# simplePDschematicsv1_AZ_SMD.net
KiCad netlist of a schematic drawn in EAGLE
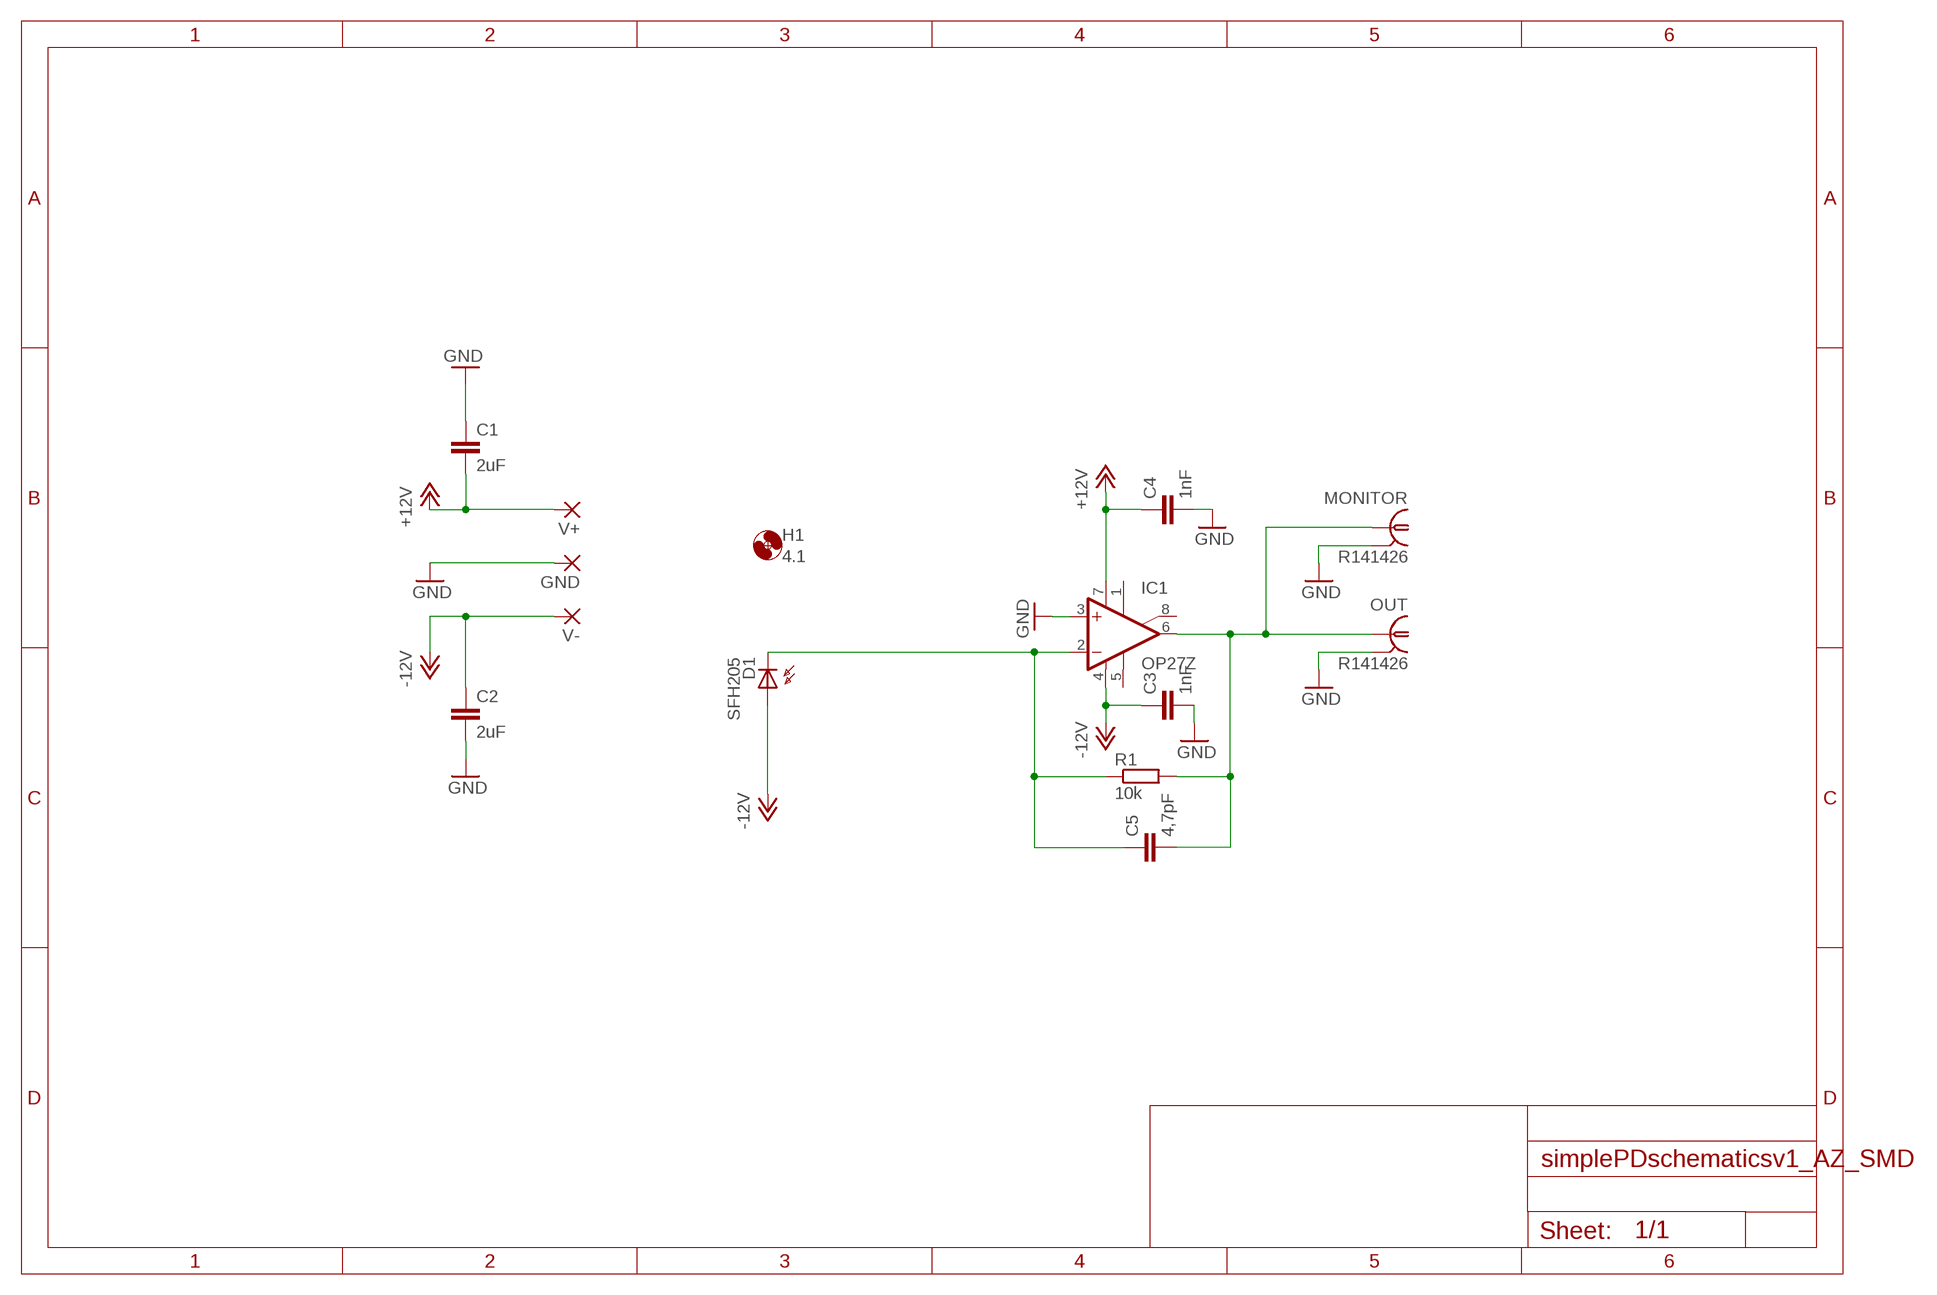
[diagram p0: schematic, sheet 1]

(export (version "E")
  (design (tool "Eeschema 10.0.6"))
  (components
    (comp (ref "C1")
      (value "2uF")
      (footprint "eagle-import:C050-075X075")
      (libsource (lib "eagle-import") (part "C-EU050-075X075"))
    )
    (comp (ref "C2")
      (value "2uF")
      (footprint "eagle-import:C050-075X075")
      (libsource (lib "eagle-import") (part "C-EU050-075X075"))
    )
    (comp (ref "C3")
      (value "1nF")
      (footprint "eagle-import:C025-050X050")
      (libsource (lib "eagle-import") (part "C-EU025-050X050"))
    )
    (comp (ref "C4")
      (value "1nF")
      (footprint "eagle-import:C025-050X050")
      (libsource (lib "eagle-import") (part "C-EU025-050X050"))
    )
    (comp (ref "C5")
      (value "4,7pF")
      (footprint "eagle-import:C025-050X050")
      (libsource (lib "eagle-import") (part "C-EU025-050X050"))
    )
    (comp (ref "D1")
      (value "SFH205")
      (footprint "eagle-import:SFH205")
      (libsource (lib "eagle-import") (part "SFH205"))
    )
    (comp (ref "GND")
      (value "1,6/0,9")
      (footprint "eagle-import:1,6_0,9")
      (libsource (lib "eagle-import") (part "1,6/0,9"))
    )
    (comp (ref "H1")
      (value "4.1")
      (footprint "eagle-import:4,1")
      (libsource (lib "eagle-import") (part "MOUNT-HOLE4.1"))
    )
    (comp (ref "IC1")
      (value "OP27Z")
      (footprint "eagle-import:DIL08")
      (libsource (lib "eagle-import") (part "OP27Z"))
    )
    (comp (ref "MONITOR")
      (value "R141426")
      (footprint "eagle-import:R141426")
      (fields (field (name "MF") "FARNELL") (field (name "MPN") "R141426161"))
      (libsource (lib "eagle-import") (part "R141426"))
    )
    (comp (ref "OUT")
      (value "R141426")
      (footprint "eagle-import:R141426")
      (fields (field (name "MF") "FARNELL") (field (name "MPN") "R141426161"))
      (libsource (lib "eagle-import") (part "R141426"))
    )
    (comp (ref "R1")
      (value "10k")
      (footprint "eagle-import:M1206")
      (libsource (lib "eagle-import") (part "R-EU_M1206"))
    )
    (comp (ref "V+")
      (value "1,6/0,9")
      (footprint "eagle-import:1,6_0,9")
      (libsource (lib "eagle-import") (part "1,6/0,9"))
    )
    (comp (ref "V-")
      (value "1,6/0,9")
      (footprint "eagle-import:1,6_0,9")
      (libsource (lib "eagle-import") (part "1,6/0,9"))
    )
  )
  (nets
    (net (code "1") (name "+12V") (class "Default")
      (node (ref "C1") (pin "2") (pinfunction "2_2") (pintype "passive"))
      (node (ref "C4") (pin "1") (pinfunction "1_1") (pintype "passive"))
      (node (ref "IC1") (pin "7") (pinfunction "V+_7") (pintype "power_in"))
      (node (ref "V+") (pin "1") (pinfunction "P_1") (pintype "passive"))
    )
    (net (code "2") (name "-12V") (class "Default")
      (node (ref "C2") (pin "1") (pinfunction "1_1") (pintype "passive"))
      (node (ref "C3") (pin "1") (pinfunction "1_1") (pintype "passive"))
      (node (ref "D1") (pin "A") (pinfunction "A_A") (pintype "passive"))
      (node (ref "IC1") (pin "4") (pinfunction "V-_4") (pintype "power_in"))
      (node (ref "V-") (pin "1") (pinfunction "P_1") (pintype "passive"))
    )
    (net (code "3") (name "GND") (class "Default")
      (node (ref "C1") (pin "1") (pinfunction "1_1") (pintype "passive"))
      (node (ref "C2") (pin "2") (pinfunction "2_2") (pintype "passive"))
      (node (ref "C3") (pin "2") (pinfunction "2_2") (pintype "passive"))
      (node (ref "C4") (pin "2") (pinfunction "2_2") (pintype "passive"))
      (node (ref "GND") (pin "1") (pinfunction "P_1") (pintype "passive"))
      (node (ref "IC1") (pin "3") (pinfunction "+IN_3") (pintype "input"))
      (node (ref "MONITOR") (pin "2") (pinfunction "2_2") (pintype "passive"))
      (node (ref "MONITOR") (pin "3") (pinfunction "2_3") (pintype "passive"))
      (node (ref "MONITOR") (pin "4") (pinfunction "2_4") (pintype "passive"))
      (node (ref "MONITOR") (pin "5") (pinfunction "2_5") (pintype "passive"))
      (node (ref "OUT") (pin "2") (pinfunction "2_2") (pintype "passive"))
      (node (ref "OUT") (pin "3") (pinfunction "2_3") (pintype "passive"))
      (node (ref "OUT") (pin "4") (pinfunction "2_4") (pintype "passive"))
      (node (ref "OUT") (pin "5") (pinfunction "2_5") (pintype "passive"))
    )
    (net (code "4") (name "Net-(D1-C)") (class "Default")
      (node (ref "C5") (pin "1") (pinfunction "1_1") (pintype "passive"))
      (node (ref "D1") (pin "K") (pinfunction "C_K") (pintype "passive"))
      (node (ref "IC1") (pin "2") (pinfunction "-IN_2") (pintype "input"))
      (node (ref "R1") (pin "1") (pinfunction "1_1") (pintype "passive"))
    )
    (net (code "5") (name "Net-(IC1-OUT)") (class "Default")
      (node (ref "C5") (pin "2") (pinfunction "2_2") (pintype "passive"))
      (node (ref "IC1") (pin "6") (pinfunction "OUT_6") (pintype "output"))
      (node (ref "MONITOR") (pin "1") (pinfunction "1_1") (pintype "passive"))
      (node (ref "OUT") (pin "1") (pinfunction "1_1") (pintype "passive"))
      (node (ref "R1") (pin "2") (pinfunction "2_2") (pintype "passive"))
    )
    (net (code "6") (name "unconnected-(IC1-ON1-Pad1)") (class "Default")
      (node (ref "IC1") (pin "1") (pinfunction "ON1_1") (pintype "passive"))
    )
    (net (code "7") (name "unconnected-(IC1-ON2-Pad8)") (class "Default")
      (node (ref "IC1") (pin "8") (pinfunction "ON2_8") (pintype "passive"))
    )
    (net (code "8") (name "unconnected-(IC1-OPT-Pad5)") (class "Default")
      (node (ref "IC1") (pin "5") (pinfunction "OPT_5") (pintype "passive"))
    )
  )
)
